# ESP32.net
KiCad netlist of a schematic drawn in Altium Designer
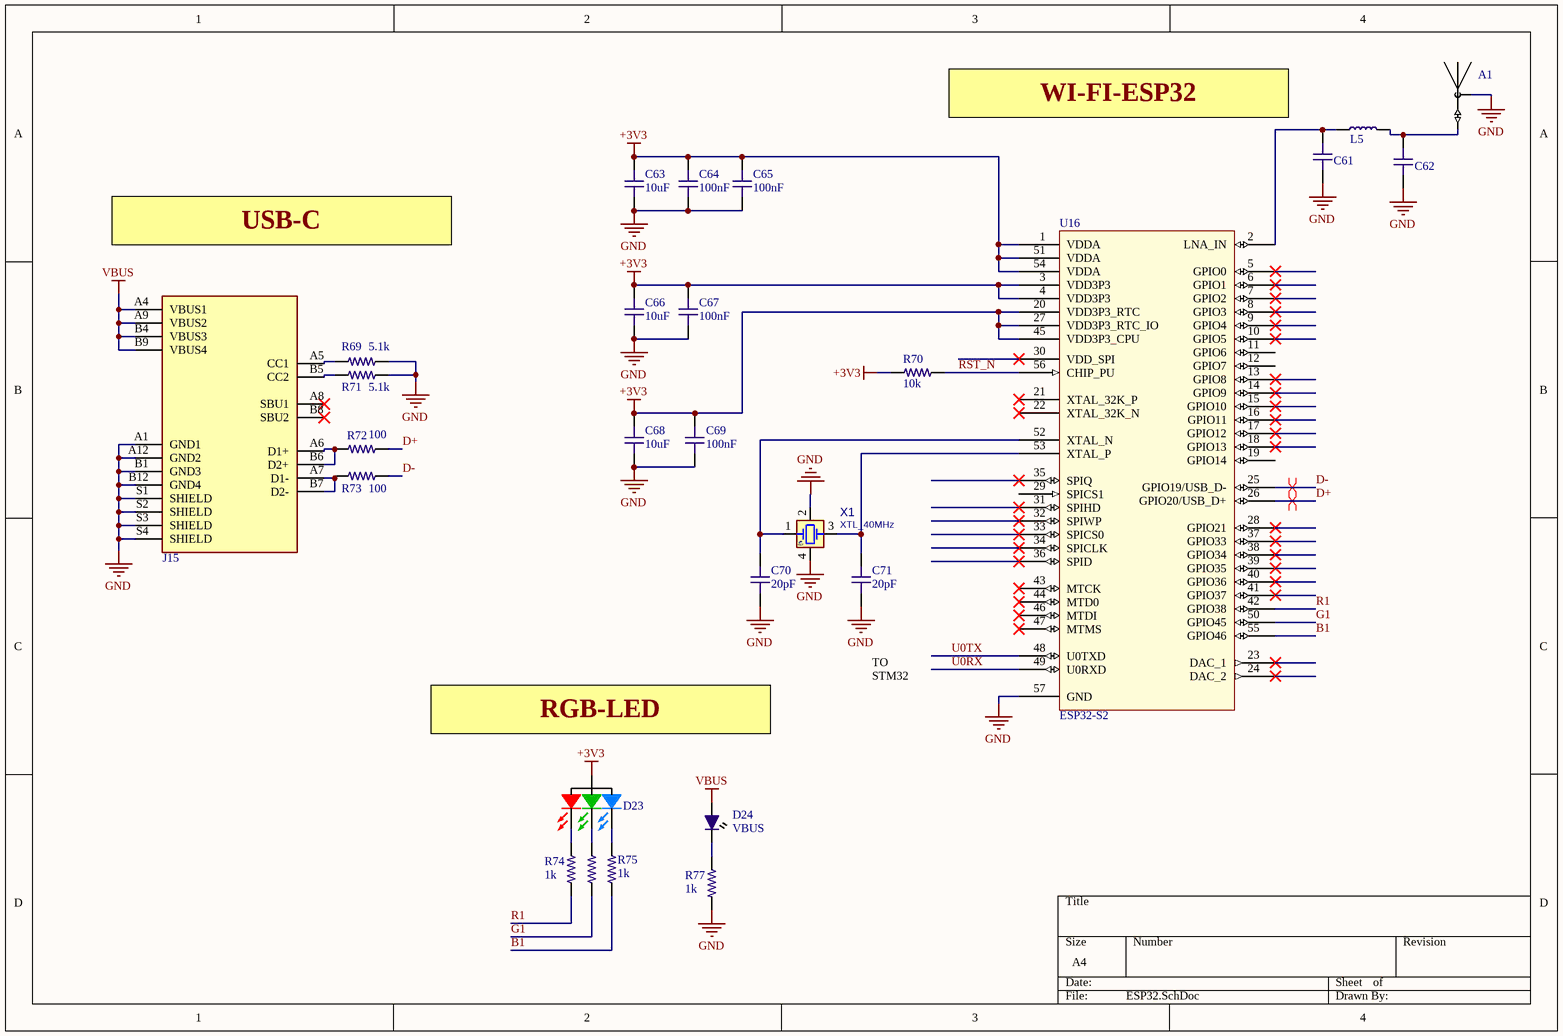
[diagram p0: ESP32.SchDoc]

(export (version "E")
  (design (tool "Eeschema 10.0.6"))
  (components
    (comp (ref "A1")
      (value "0479480001")
      (footprint "0479480001")
      (description "2.4GHz Bluetooth, WLAN, Zigbee™ Chip RF Antenna 2.4GHz ~ 2.483.5GHz 3dBi Solder Surface Mount")
      (libsource (lib "RF Components") (part "Molex 0479480001"))
    )
    (comp (ref "C61")
      (value "0402 Capacitor Template")
      (footprint "C0402-HIGH-DENSITY")
      (description "Chip Capacitor, 0402, ??nF, 10V, X7R")
      (libsource (lib "Capacitors") (part "0402 Capacitor Template"))
    )
    (comp (ref "C62")
      (value "0402 Capacitor Template")
      (footprint "C0402-HIGH-DENSITY")
      (description "Chip Capacitor, 0402, ??nF, 10V, X7R")
      (libsource (lib "Capacitors") (part "0402 Capacitor Template"))
    )
    (comp (ref "C63")
      (value "10uF")
      (footprint "C0402-HIGH-DENSITY")
      (description "Chip Capacitor, 0402, 10uF, 10V, X5R")
      (fields (field (name "Comment") "C0402 10uF 10V"))
      (libsource (lib "Capacitors") (part "C0402 10uF 10V"))
    )
    (comp (ref "C64")
      (value "100nF")
      (footprint "C0402-HIGH-DENSITY")
      (description "Chip Capacitor, 0402, 100nF, 10V, X5R")
      (fields (field (name "Comment") "C0402 100nF 10V X5R"))
      (libsource (lib "Capacitors") (part "C0402 100nF 10V X5R"))
    )
    (comp (ref "C65")
      (value "100nF")
      (footprint "C0402-HIGH-DENSITY")
      (description "Chip Capacitor, 0402, 100nF, 10V, X5R")
      (fields (field (name "Comment") "C0402 100nF 10V X5R"))
      (libsource (lib "Capacitors") (part "C0402 100nF 10V X5R"))
    )
    (comp (ref "C66")
      (value "10uF")
      (footprint "C0402-HIGH-DENSITY")
      (description "Chip Capacitor, 0402, 10uF, 10V, X5R")
      (fields (field (name "Comment") "C0402 10uF 10V"))
      (libsource (lib "Capacitors") (part "C0402 10uF 10V"))
    )
    (comp (ref "C67")
      (value "100nF")
      (footprint "C0402-HIGH-DENSITY")
      (description "Chip Capacitor, 0402, 100nF, 10V, X5R")
      (fields (field (name "Comment") "C0402 100nF 10V X5R"))
      (libsource (lib "Capacitors") (part "C0402 100nF 10V X5R"))
    )
    (comp (ref "C68")
      (value "10uF")
      (footprint "C0402-HIGH-DENSITY")
      (description "Chip Capacitor, 0402, 10uF, 10V, X5R")
      (fields (field (name "Comment") "C0402 10uF 10V"))
      (libsource (lib "Capacitors") (part "C0402 10uF 10V"))
    )
    (comp (ref "C69")
      (value "100nF")
      (footprint "C0402-HIGH-DENSITY")
      (description "Chip Capacitor, 0402, 100nF, 10V, X5R")
      (fields (field (name "Comment") "C0402 100nF 10V X5R"))
      (libsource (lib "Capacitors") (part "C0402 100nF 10V X5R"))
    )
    (comp (ref "C70")
      (value "20pF")
      (footprint "C0402-HIGH-DENSITY")
      (description "Chip Capacitor, 0402, 100nF, 10V, X5R")
      (fields (field (name "Comment") "C0402 100nF 10V X5R"))
      (libsource (lib "Capacitors") (part "C0402 100nF 10V X5R"))
    )
    (comp (ref "C71")
      (value "20pF")
      (footprint "C0402-HIGH-DENSITY")
      (description "Chip Capacitor, 0402, 100nF, 10V, X5R")
      (fields (field (name "Comment") "C0402 100nF 10V X5R"))
      (libsource (lib "Capacitors") (part "C0402 100nF 10V X5R"))
    )
    (comp (ref "D23")
      (value "RGB")
      (footprint "Pcb-hionyPcbLib:RGB-LED")
      (description "RGB Led 1.6 x 1.6 mm Diffused")
      (fields
        (field (name "MANUFACTURER") "Everlight")
        (field (name "MANUFACTURER PART NUMBER") "19-237/R6GHBHW-C01/2T")
      )
      (libsource (lib "lib-hiony") (part "Led_RGB_0606"))
    )
    (comp (ref "D24")
      (value "VBUS")
      (footprint "LED0603-IPC")
      (description "LED YELLOW CLEAR 0603 SMD")
      (libsource (lib "Diodes") (part "LED 0603 Yellow"))
    )
    (comp (ref "J15")
      (value "16 Pin Mid Mount USB C")
      (footprint "USB-C - 16 Pin Mid Mount")
      (description "USB-C USB 2.0 5A PD 16 Position Mid Mount")
      (fields (field (name "MANUFACTURER") "Jing Extension of the Electronic Co"))
      (libsource (lib "Connectors") (part "USB C USB 2.0 and PD"))
    )
    (comp (ref "L5")
      (value "! Inductor Template")
      (footprint "L0402-Murata-WW-High-Density")
      (description "Inductor, ??uH")
      (libsource (lib "Inductors") (part "! Inductor Template"))
    )
    (comp (ref "R69")
      (value "5.1k")
      (footprint "R0402-HIGH-DENSITY")
      (description "RES SMD 5.1K OHM 1% 1/10W 0402")
      (fields (field (name "Comment") "R0402 5.1K 1%"))
      (libsource (lib "Resistors") (part "R0402 5.1K 1%"))
    )
    (comp (ref "R70")
      (value "10k")
      (footprint "R0402-HIGH-DENSITY")
      (description "Chip Resistor, 0402, 10k ohms, 1%, 1/16 W")
      (fields (field (name "Comment") "R0402 10k 1%"))
      (libsource (lib "Resistors") (part "R0402 10k 1%"))
    )
    (comp (ref "R71")
      (value "5.1k")
      (footprint "R0402-HIGH-DENSITY")
      (description "RES SMD 5.1K OHM 1% 1/10W 0402")
      (fields (field (name "Comment") "R0402 5.1K 1%"))
      (libsource (lib "Resistors") (part "R0402 5.1K 1%"))
    )
    (comp (ref "R72")
      (value "100")
      (footprint "R0402-HIGH-DENSITY")
      (description "Chip Resistor, 0402, 100 ohms, 1%, 1/16 W")
      (fields (field (name "Comment") "R0402 100R 1%"))
      (libsource (lib "Resistors") (part "R0402 100R 1%"))
    )
    (comp (ref "R73")
      (value "100")
      (footprint "R0402-HIGH-DENSITY")
      (description "Chip Resistor, 0402, 100 ohms, 1%, 1/16 W")
      (fields (field (name "Comment") "R0402 100R 1%"))
      (libsource (lib "Resistors") (part "R0402 100R 1%"))
    )
    (comp (ref "R74")
      (value "1k")
      (footprint "R0402-HIGH-DENSITY")
      (description "Chip Resistor, 0402, 1k ohms, 1%, 1/16 W")
      (fields (field (name "Comment") "R0402 1k 1%"))
      (libsource (lib "Resistors") (part "R0402 1k 1%"))
    )
    (comp (ref "R75")
      (value "1k")
      (footprint "R0402-HIGH-DENSITY")
      (description "Chip Resistor, 0402, 1k ohms, 1%, 1/16 W")
      (fields (field (name "Comment") "R0402 1k 1%"))
      (libsource (lib "Resistors") (part "R0402 1k 1%"))
    )
    (comp (ref "R76")
      (value "R0402 1k 1%")
      (footprint "R0402-HIGH-DENSITY")
      (description "Chip Resistor, 0402, 1k ohms, 1%, 1/16 W")
      (libsource (lib "Resistors") (part "R0402 1k 1%"))
    )
    (comp (ref "R77")
      (value "1k")
      (footprint "R0402-HIGH-DENSITY")
      (description "Chip Resistor, 0402, 1k ohms, 1%, 1/16 W")
      (fields (field (name "Comment") "R0402 1k 1%"))
      (libsource (lib "Resistors") (part "R0402 1k 1%"))
    )
    (comp (ref "U16")
      (value "ESP32-S2")
      (footprint "QFN56")
      (description "WiFi 802.11b/g/n Transceiver Module 2.4GHz QFN-56")
      (libsource (lib "Integrated Circuits") (part "ESP32-S2"))
    )
    (comp (ref "X1")
      (value "XTL_40MHz")
      (footprint "XTL_4_2016")
      (description "CRYSTAL 40.00 MHZ 7pF, 10PPM")
      (fields (field (name "MANF") "DIODES") (field (name "MANF_P#") "FW400WFQA1"))
      (libsource (lib "crystal") (part "XTL_4_40MHz_2016F"))
    )
  )
  (nets
    (net (code "1") (name "+3V3") (class "Default")
      (node (ref "C63") (pin "2") (pintype "passive"))
      (node (ref "C64") (pin "2") (pintype "passive"))
      (node (ref "C65") (pin "2") (pintype "passive"))
      (node (ref "C66") (pin "2") (pintype "passive"))
      (node (ref "C67") (pin "2") (pintype "passive"))
      (node (ref "C68") (pin "2") (pintype "passive"))
      (node (ref "C69") (pin "2") (pintype "passive"))
      (node (ref "D23") (pin "A") (pinfunction "A_A") (pintype "passive"))
      (node (ref "R70") (pin "1") (pintype "passive"))
      (node (ref "U16") (pin "1") (pinfunction "VDDA_1") (pintype "power_in"))
      (node (ref "U16") (pin "20") (pinfunction "VDD3P3_RTC_20") (pintype "power_in"))
      (node (ref "U16") (pin "27") (pinfunction "VDD3P3_RTC_IO_27") (pintype "power_in"))
      (node (ref "U16") (pin "3") (pinfunction "VDD3P3_3") (pintype "power_in"))
      (node (ref "U16") (pin "4") (pinfunction "VDD3P3_4") (pintype "power_in"))
      (node (ref "U16") (pin "45") (pinfunction "VDD3P3_CPU_45") (pintype "power_in"))
      (node (ref "U16") (pin "51") (pinfunction "VDDA_51") (pintype "power_in"))
      (node (ref "U16") (pin "54") (pinfunction "VDDA_54") (pintype "power_in"))
    )
    (net (code "2") (name "/B1") (class "Default")
      (node (ref "R75") (pin "1") (pintype "passive"))
      (node (ref "U16") (pin "55") (pinfunction "GPIO46_55") (pintype "bidirectional"))
    )
    (net (code "3") (name "/D+") (class "Default")
      (node (ref "R72") (pin "2") (pintype "passive"))
      (node (ref "U16") (pin "26") (pinfunction "GPIO20/USB_D+_26") (pintype "bidirectional"))
    )
    (net (code "4") (name "/D-") (class "Default")
      (node (ref "R73") (pin "2") (pintype "passive"))
      (node (ref "U16") (pin "25") (pinfunction "GPIO19/USB_D-_25") (pintype "bidirectional"))
    )
    (net (code "5") (name "/G1") (class "Default")
      (node (ref "R76") (pin "1") (pintype "passive"))
      (node (ref "U16") (pin "50") (pinfunction "GPIO45_50") (pintype "bidirectional"))
    )
    (net (code "6") (name "/R1") (class "Default")
      (node (ref "R74") (pin "1") (pintype "passive"))
      (node (ref "U16") (pin "42") (pinfunction "GPIO38_42") (pintype "bidirectional"))
    )
    (net (code "7") (name "/RST_N") (class "Default")
      (node (ref "R70") (pin "2") (pintype "passive"))
      (node (ref "U16") (pin "56") (pinfunction "CHIP_PU_56") (pintype "input"))
    )
    (net (code "8") (name "/U0RX") (class "Default")
      (node (ref "U16") (pin "49") (pinfunction "U0RXD_49") (pintype "bidirectional"))
    )
    (net (code "9") (name "/U0TX") (class "Default")
      (node (ref "U16") (pin "48") (pinfunction "U0TXD_48") (pintype "bidirectional"))
    )
    (net (code "10") (name "GND") (class "Default")
      (node (ref "A1") (pin "2") (pinfunction "2_2") (pintype "power_in"))
      (node (ref "C61") (pin "1") (pintype "passive"))
      (node (ref "C62") (pin "1") (pintype "passive"))
      (node (ref "C63") (pin "1") (pintype "passive"))
      (node (ref "C64") (pin "1") (pintype "passive"))
      (node (ref "C65") (pin "1") (pintype "passive"))
      (node (ref "C66") (pin "1") (pintype "passive"))
      (node (ref "C67") (pin "1") (pintype "passive"))
      (node (ref "C68") (pin "1") (pintype "passive"))
      (node (ref "C69") (pin "1") (pintype "passive"))
      (node (ref "C70") (pin "1") (pintype "passive"))
      (node (ref "C71") (pin "1") (pintype "passive"))
      (node (ref "J15") (pin "A1") (pinfunction "GND1_A1") (pintype "passive"))
      (node (ref "J15") (pin "A12") (pinfunction "GND2_A12") (pintype "passive"))
      (node (ref "J15") (pin "B1") (pinfunction "GND3_B1") (pintype "passive"))
      (node (ref "J15") (pin "B12") (pinfunction "GND4_B12") (pintype "passive"))
      (node (ref "J15") (pin "S1") (pinfunction "SHIELD_S1") (pintype "passive"))
      (node (ref "J15") (pin "S2") (pinfunction "SHIELD_S2") (pintype "passive"))
      (node (ref "J15") (pin "S3") (pinfunction "SHIELD_S3") (pintype "passive"))
      (node (ref "J15") (pin "S4") (pinfunction "SHIELD_S4") (pintype "passive"))
      (node (ref "R69") (pin "2") (pintype "passive"))
      (node (ref "R71") (pin "2") (pintype "passive"))
      (node (ref "R77") (pin "1") (pintype "passive"))
      (node (ref "U16") (pin "57") (pinfunction "GND_57") (pintype "power_in"))
      (node (ref "X1") (pin "2") (pinfunction "GND1_2") (pintype "passive"))
      (node (ref "X1") (pin "4") (pinfunction "GND2_4") (pintype "passive"))
    )
    (net (code "11") (name "Net-(A1-FEED)") (class "Default")
      (node (ref "A1") (pin "1") (pinfunction "FEED_1") (pintype "bidirectional"))
      (node (ref "C62") (pin "2") (pintype "passive"))
      (node (ref "L5") (pin "2") (pintype "passive"))
    )
    (net (code "12") (name "Net-(D23-PadBK)") (class "Default")
      (node (ref "D23") (pin "BK") (pinfunction "BK_BK") (pintype "passive"))
      (node (ref "R75") (pin "2") (pintype "passive"))
    )
    (net (code "13") (name "Net-(D23-PadGK)") (class "Default")
      (node (ref "D23") (pin "GK") (pinfunction "GK_GK") (pintype "passive"))
      (node (ref "R76") (pin "2") (pintype "passive"))
    )
    (net (code "14") (name "Net-(D23-PadRK)") (class "Default")
      (node (ref "D23") (pin "RK") (pinfunction "RK_RK") (pintype "passive"))
      (node (ref "R74") (pin "2") (pintype "passive"))
    )
    (net (code "15") (name "Net-(D24-PadK)") (class "Default")
      (node (ref "D24") (pin "K") (pintype "passive"))
      (node (ref "R77") (pin "2") (pintype "passive"))
    )
    (net (code "16") (name "Net-(J15-CC1)") (class "Default")
      (node (ref "J15") (pin "A5") (pinfunction "CC1_A5") (pintype "passive"))
      (node (ref "R69") (pin "1") (pintype "passive"))
    )
    (net (code "17") (name "Net-(J15-CC2)") (class "Default")
      (node (ref "J15") (pin "B5") (pinfunction "CC2_B5") (pintype "passive"))
      (node (ref "R71") (pin "1") (pintype "passive"))
    )
    (net (code "18") (name "Net-(J15-D1+)") (class "Default")
      (node (ref "J15") (pin "A6") (pinfunction "D1+_A6") (pintype "passive"))
      (node (ref "J15") (pin "B6") (pinfunction "D2+_B6") (pintype "passive"))
      (node (ref "R72") (pin "1") (pintype "passive"))
    )
    (net (code "19") (name "Net-(J15-D1-)") (class "Default")
      (node (ref "J15") (pin "A7") (pinfunction "D1-_A7") (pintype "passive"))
      (node (ref "J15") (pin "B7") (pinfunction "D2-_B7") (pintype "passive"))
      (node (ref "R73") (pin "1") (pintype "passive"))
    )
    (net (code "20") (name "Net-(U16-LNA_IN)") (class "Default")
      (node (ref "C61") (pin "2") (pintype "passive"))
      (node (ref "L5") (pin "1") (pintype "passive"))
      (node (ref "U16") (pin "2") (pinfunction "LNA_IN_2") (pintype "bidirectional"))
    )
    (net (code "21") (name "Net-(U16-XTAL_N)") (class "Default")
      (node (ref "C70") (pin "2") (pintype "passive"))
      (node (ref "U16") (pin "52") (pinfunction "XTAL_N_52") (pintype "passive"))
      (node (ref "X1") (pin "1") (pinfunction "XA_1") (pintype "passive"))
    )
    (net (code "22") (name "Net-(U16-XTAL_P)") (class "Default")
      (node (ref "C71") (pin "2") (pintype "passive"))
      (node (ref "U16") (pin "53") (pinfunction "XTAL_P_53") (pintype "passive"))
      (node (ref "X1") (pin "3") (pinfunction "XB_3") (pintype "passive"))
    )
    (net (code "23") (name "VBUS") (class "Default")
      (node (ref "D24") (pin "A") (pintype "passive"))
      (node (ref "J15") (pin "A4") (pinfunction "VBUS1_A4") (pintype "passive"))
      (node (ref "J15") (pin "A9") (pinfunction "VBUS2_A9") (pintype "passive"))
      (node (ref "J15") (pin "B4") (pinfunction "VBUS3_B4") (pintype "passive"))
      (node (ref "J15") (pin "B9") (pinfunction "VBUS4_B9") (pintype "passive"))
    )
    (net (code "24") (name "unconnected-(J15-SBU1-PadA8)") (class "Default")
      (node (ref "J15") (pin "A8") (pinfunction "SBU1_A8") (pintype "passive+no_connect"))
    )
    (net (code "25") (name "unconnected-(J15-SBU2-PadB8)") (class "Default")
      (node (ref "J15") (pin "B8") (pinfunction "SBU2_B8") (pintype "passive+no_connect"))
    )
    (net (code "26") (name "unconnected-(U16-DAC_1-Pad23)") (class "Default")
      (node (ref "U16") (pin "23") (pinfunction "DAC_1_23") (pintype "output+no_connect"))
    )
    (net (code "27") (name "unconnected-(U16-DAC_2-Pad24)") (class "Default")
      (node (ref "U16") (pin "24") (pinfunction "DAC_2_24") (pintype "output+no_connect"))
    )
    (net (code "28") (name "unconnected-(U16-GPIO0-Pad5)") (class "Default")
      (node (ref "U16") (pin "5") (pinfunction "GPIO0_5") (pintype "bidirectional+no_connect"))
    )
    (net (code "29") (name "unconnected-(U16-GPIO1-Pad6)") (class "Default")
      (node (ref "U16") (pin "6") (pinfunction "GPIO1_6") (pintype "bidirectional+no_connect"))
    )
    (net (code "30") (name "unconnected-(U16-GPIO2-Pad7)") (class "Default")
      (node (ref "U16") (pin "7") (pinfunction "GPIO2_7") (pintype "bidirectional+no_connect"))
    )
    (net (code "31") (name "unconnected-(U16-GPIO3-Pad8)") (class "Default")
      (node (ref "U16") (pin "8") (pinfunction "GPIO3_8") (pintype "bidirectional+no_connect"))
    )
    (net (code "32") (name "unconnected-(U16-GPIO4-Pad9)") (class "Default")
      (node (ref "U16") (pin "9") (pinfunction "GPIO4_9") (pintype "bidirectional+no_connect"))
    )
    (net (code "33") (name "unconnected-(U16-GPIO5-Pad10)") (class "Default")
      (node (ref "U16") (pin "10") (pinfunction "GPIO5_10") (pintype "bidirectional+no_connect"))
    )
    (net (code "34") (name "unconnected-(U16-GPIO6-Pad11)") (class "Default")
      (node (ref "U16") (pin "11") (pinfunction "GPIO6_11") (pintype "bidirectional"))
    )
    (net (code "35") (name "unconnected-(U16-GPIO7-Pad12)") (class "Default")
      (node (ref "U16") (pin "12") (pinfunction "GPIO7_12") (pintype "bidirectional"))
    )
    (net (code "36") (name "unconnected-(U16-GPIO8-Pad13)") (class "Default")
      (node (ref "U16") (pin "13") (pinfunction "GPIO8_13") (pintype "bidirectional+no_connect"))
    )
    (net (code "37") (name "unconnected-(U16-GPIO9-Pad14)") (class "Default")
      (node (ref "U16") (pin "14") (pinfunction "GPIO9_14") (pintype "bidirectional+no_connect"))
    )
    (net (code "38") (name "unconnected-(U16-GPIO10-Pad15)") (class "Default")
      (node (ref "U16") (pin "15") (pinfunction "GPIO10_15") (pintype "bidirectional+no_connect"))
    )
    (net (code "39") (name "unconnected-(U16-GPIO11-Pad16)") (class "Default")
      (node (ref "U16") (pin "16") (pinfunction "GPIO11_16") (pintype "bidirectional+no_connect"))
    )
    (net (code "40") (name "unconnected-(U16-GPIO12-Pad17)") (class "Default")
      (node (ref "U16") (pin "17") (pinfunction "GPIO12_17") (pintype "bidirectional+no_connect"))
    )
    (net (code "41") (name "unconnected-(U16-GPIO13-Pad18)") (class "Default")
      (node (ref "U16") (pin "18") (pinfunction "GPIO13_18") (pintype "bidirectional+no_connect"))
    )
    (net (code "42") (name "unconnected-(U16-GPIO14-Pad19)") (class "Default")
      (node (ref "U16") (pin "19") (pinfunction "GPIO14_19") (pintype "bidirectional"))
    )
    (net (code "43") (name "unconnected-(U16-GPIO21-Pad28)") (class "Default")
      (node (ref "U16") (pin "28") (pinfunction "GPIO21_28") (pintype "bidirectional+no_connect"))
    )
    (net (code "44") (name "unconnected-(U16-GPIO33-Pad37)") (class "Default")
      (node (ref "U16") (pin "37") (pinfunction "GPIO33_37") (pintype "bidirectional+no_connect"))
    )
    (net (code "45") (name "unconnected-(U16-GPIO34-Pad38)") (class "Default")
      (node (ref "U16") (pin "38") (pinfunction "GPIO34_38") (pintype "bidirectional+no_connect"))
    )
    (net (code "46") (name "unconnected-(U16-GPIO35-Pad39)") (class "Default")
      (node (ref "U16") (pin "39") (pinfunction "GPIO35_39") (pintype "bidirectional+no_connect"))
    )
    (net (code "47") (name "unconnected-(U16-GPIO36-Pad40)") (class "Default")
      (node (ref "U16") (pin "40") (pinfunction "GPIO36_40") (pintype "bidirectional+no_connect"))
    )
    (net (code "48") (name "unconnected-(U16-GPIO37-Pad41)") (class "Default")
      (node (ref "U16") (pin "41") (pinfunction "GPIO37_41") (pintype "bidirectional+no_connect"))
    )
    (net (code "49") (name "unconnected-(U16-MTCK-Pad43)") (class "Default")
      (node (ref "U16") (pin "43") (pinfunction "MTCK_43") (pintype "bidirectional+no_connect"))
    )
    (net (code "50") (name "unconnected-(U16-MTD0-Pad44)") (class "Default")
      (node (ref "U16") (pin "44") (pinfunction "MTD0_44") (pintype "bidirectional+no_connect"))
    )
    (net (code "51") (name "unconnected-(U16-MTDI-Pad46)") (class "Default")
      (node (ref "U16") (pin "46") (pinfunction "MTDI_46") (pintype "bidirectional+no_connect"))
    )
    (net (code "52") (name "unconnected-(U16-MTMS-Pad47)") (class "Default")
      (node (ref "U16") (pin "47") (pinfunction "MTMS_47") (pintype "bidirectional+no_connect"))
    )
    (net (code "53") (name "unconnected-(U16-SPICLK-Pad34)") (class "Default")
      (node (ref "U16") (pin "34") (pinfunction "SPICLK_34") (pintype "bidirectional+no_connect"))
    )
    (net (code "54") (name "unconnected-(U16-SPICS0-Pad33)") (class "Default")
      (node (ref "U16") (pin "33") (pinfunction "SPICS0_33") (pintype "bidirectional+no_connect"))
    )
    (net (code "55") (name "unconnected-(U16-SPICS1-Pad29)") (class "Default")
      (node (ref "U16") (pin "29") (pinfunction "SPICS1_29") (pintype "input"))
    )
    (net (code "56") (name "unconnected-(U16-SPID-Pad36)") (class "Default")
      (node (ref "U16") (pin "36") (pinfunction "SPID_36") (pintype "bidirectional+no_connect"))
    )
    (net (code "57") (name "unconnected-(U16-SPIHD-Pad31)") (class "Default")
      (node (ref "U16") (pin "31") (pinfunction "SPIHD_31") (pintype "bidirectional+no_connect"))
    )
    (net (code "58") (name "unconnected-(U16-SPIQ-Pad35)") (class "Default")
      (node (ref "U16") (pin "35") (pinfunction "SPIQ_35") (pintype "bidirectional+no_connect"))
    )
    (net (code "59") (name "unconnected-(U16-SPIWP-Pad32)") (class "Default")
      (node (ref "U16") (pin "32") (pinfunction "SPIWP_32") (pintype "bidirectional+no_connect"))
    )
    (net (code "60") (name "unconnected-(U16-VDD_SPI-Pad30)") (class "Default")
      (node (ref "U16") (pin "30") (pinfunction "VDD_SPI_30") (pintype "power_in+no_connect"))
    )
    (net (code "61") (name "unconnected-(U16-XTAL_32K_N-Pad22)") (class "Default")
      (node (ref "U16") (pin "22") (pinfunction "XTAL_32K_N_22") (pintype "passive+no_connect"))
    )
    (net (code "62") (name "unconnected-(U16-XTAL_32K_P-Pad21)") (class "Default")
      (node (ref "U16") (pin "21") (pinfunction "XTAL_32K_P_21") (pintype "passive+no_connect"))
    )
  )
)
